# Rocket-Switch-Interface_1_011.net
KiCad netlist of a schematic drawn in EAGLE
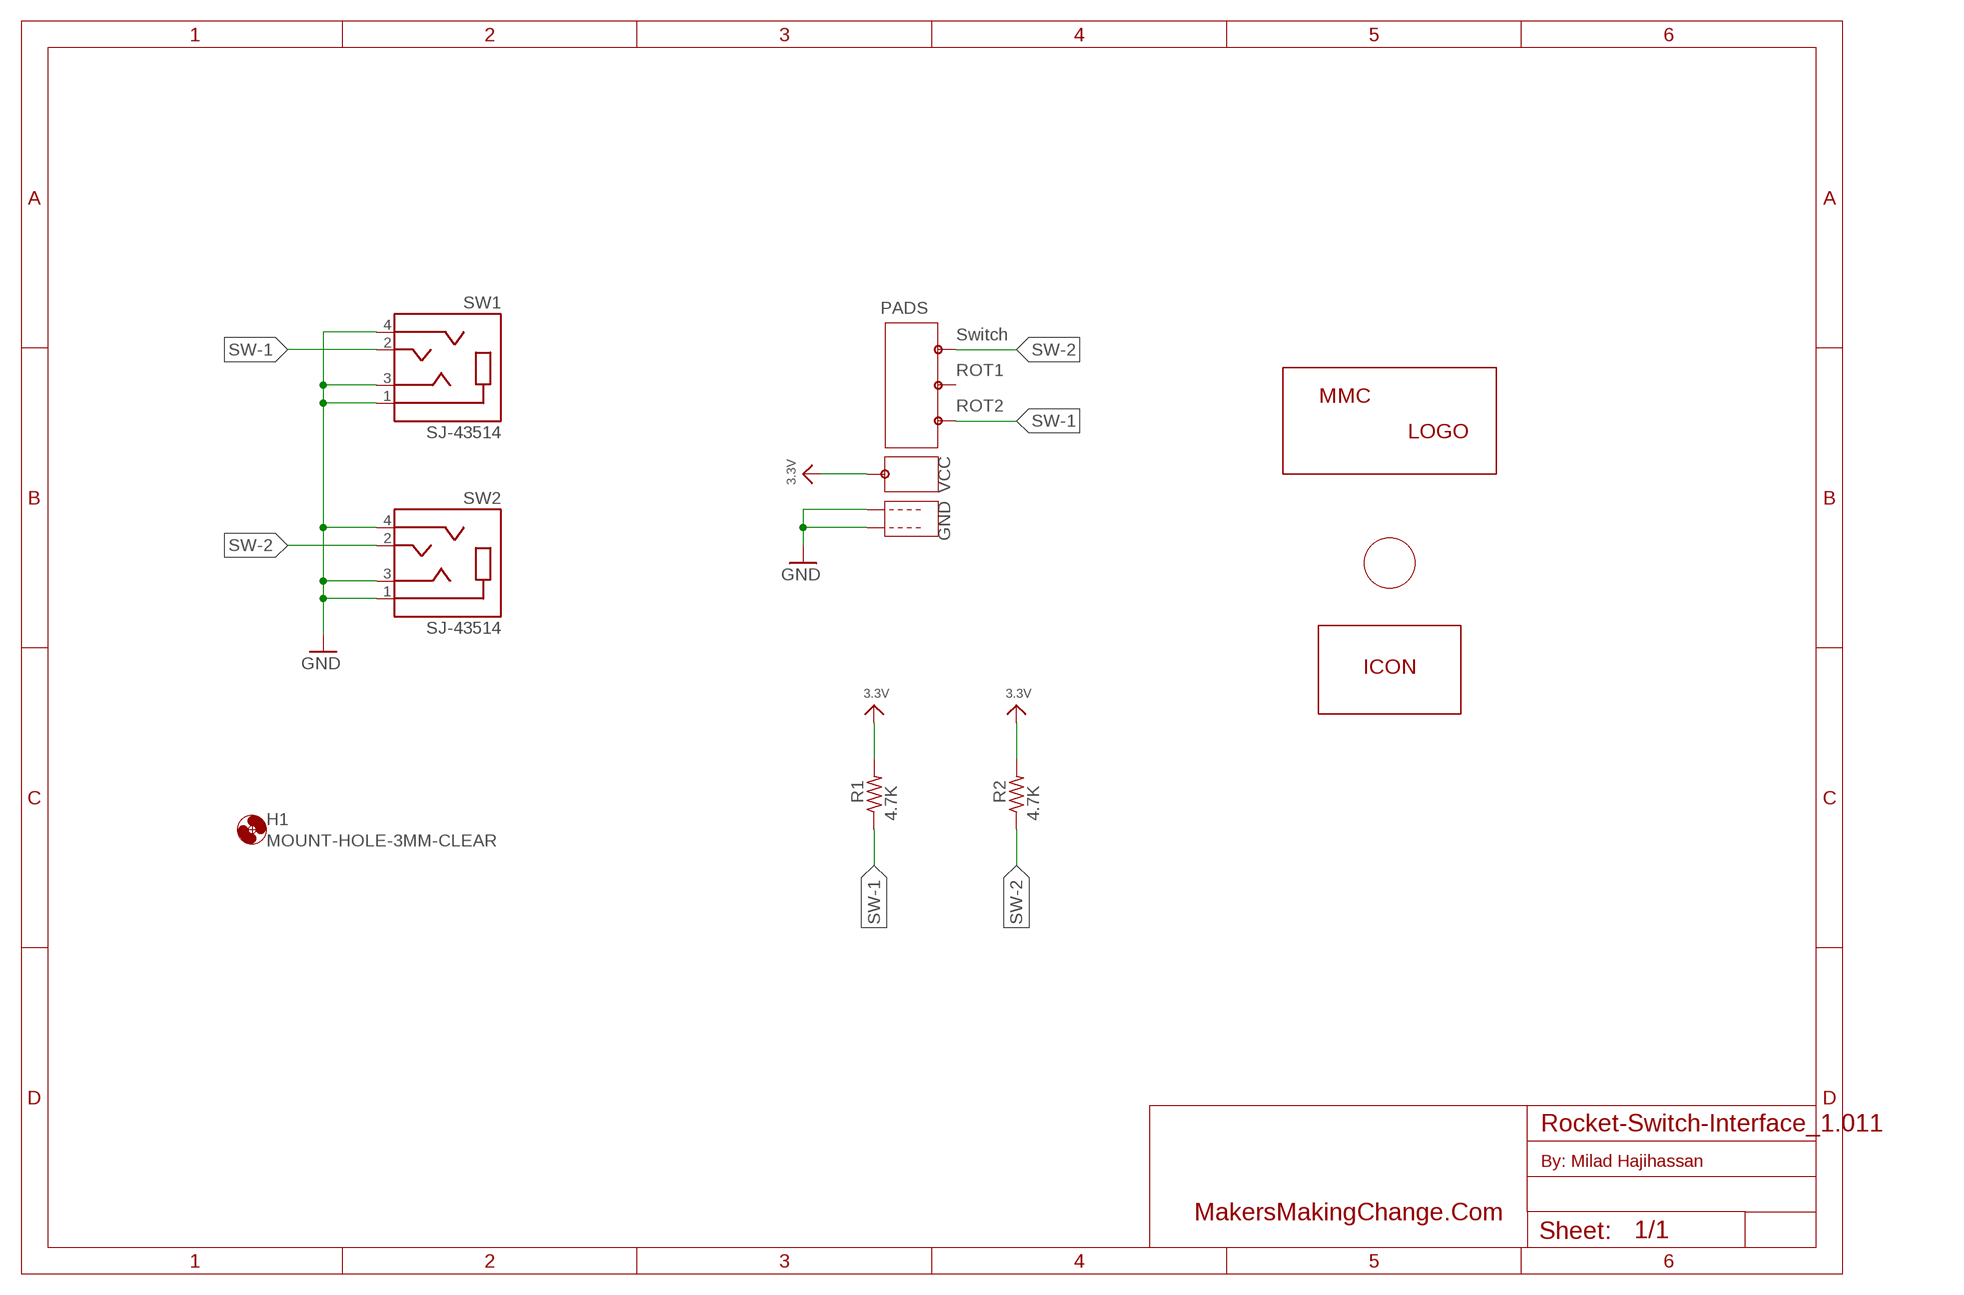
[diagram p0: schematic, sheet 1]

(export (version "E")
  (design (tool "Eeschema 10.0.6"))
  (components
    (comp (ref "H1")
      (value "MOUNT-HOLE-3MM-CLEAR")
      (footprint "eagle-import:HOLE-3MM-CLEAR")
      (libsource (lib "eagle-import") (part "MOUNT-HOLE-3MM-CLEAR"))
    )
    (comp (ref "LABEL_BACKGROUND")
      (value "MMC_ICON-ROCKET-SW")
      (footprint "eagle-import:ICON_ROCKET-SWITCH")
      (libsource (lib "eagle-import") (part "MMC_ICON-ROCKET-SW"))
    )
    (comp (ref "LABEL_DEVICE")
      (value "MMC_LABEL-ROCKET-SW")
      (footprint "eagle-import:LABEL-ROCKET-SWITCH")
      (libsource (lib "eagle-import") (part "MMC_LABEL-ROCKET-SW"))
    )
    (comp (ref "LABEL_LOGO")
      (value "MMC_LOGO-XSM")
      (footprint "eagle-import:MMC_X-SMALL_LOGO")
      (libsource (lib "eagle-import") (part "MMC_LOGO-XSM"))
    )
    (comp (ref "PADS")
      (value "PADS-ROTARY-TRINKEY-3")
      (footprint "eagle-import:PADS-ROTARY-TRINKEY-3")
      (libsource (lib "eagle-import") (part "PADS-ROTARY-TRINKEY-3"))
    )
    (comp (ref "R1")
      (value "4.7K")
      (footprint "eagle-import:RESISTOR_0204_5")
      (libsource (lib "eagle-import") (part "RESISTOR-US-0204/5"))
    )
    (comp (ref "R2")
      (value "4.7K")
      (footprint "eagle-import:RESISTOR_0204_5")
      (libsource (lib "eagle-import") (part "RESISTOR-US-0204/5"))
    )
    (comp (ref "SW1")
      (value "SJ-43514")
      (footprint "eagle-import:CUI_SJ-43514")
      (libsource (lib "eagle-import") (part "SJ-43514"))
    )
    (comp (ref "SW2")
      (value "SJ-43514")
      (footprint "eagle-import:CUI_SJ-43514")
      (libsource (lib "eagle-import") (part "SJ-43514"))
    )
  )
  (nets
    (net (code "1") (name "3.3V") (class "Default")
      (node (ref "PADS") (pin "P$VCC") (pinfunction "P$VCC_P$VCC") (pintype "passive"))
      (node (ref "R1") (pin "2") (pinfunction "2_2") (pintype "passive"))
      (node (ref "R2") (pin "2") (pinfunction "2_2") (pintype "passive"))
    )
    (net (code "2") (name "GND") (class "Default")
      (node (ref "PADS") (pin "P$GND1") (pinfunction "P$GND1_P$GND1") (pintype "passive"))
      (node (ref "PADS") (pin "P$GND2") (pinfunction "P$GND2_P$GND2") (pintype "passive"))
      (node (ref "SW1") (pin "1") (pinfunction "SLEEVE_1") (pintype "passive"))
      (node (ref "SW1") (pin "3") (pinfunction "RING1_3") (pintype "passive"))
      (node (ref "SW1") (pin "4") (pinfunction "RING2_4") (pintype "passive"))
      (node (ref "SW2") (pin "1") (pinfunction "SLEEVE_1") (pintype "passive"))
      (node (ref "SW2") (pin "3") (pinfunction "RING1_3") (pintype "passive"))
      (node (ref "SW2") (pin "4") (pinfunction "RING2_4") (pintype "passive"))
    )
    (net (code "3") (name "SW-1") (class "Default")
      (node (ref "PADS") (pin "P$ROT2") (pinfunction "P$ROT2_P$ROT2") (pintype "passive"))
      (node (ref "R1") (pin "1") (pinfunction "1_1") (pintype "passive"))
      (node (ref "SW1") (pin "2") (pinfunction "TIP_2") (pintype "passive"))
    )
    (net (code "4") (name "SW-2") (class "Default")
      (node (ref "PADS") (pin "P$SW") (pinfunction "P$SW_P$SW") (pintype "passive"))
      (node (ref "R2") (pin "1") (pinfunction "1_1") (pintype "passive"))
      (node (ref "SW2") (pin "2") (pinfunction "TIP_2") (pintype "passive"))
    )
    (net (code "5") (name "unconnected-(PADS-PadP$ROT1)") (class "Default")
      (node (ref "PADS") (pin "P$ROT1") (pinfunction "P$ROT1_P$ROT1") (pintype "passive"))
    )
  )
)
